# CW342_XADC.net
KiCad netlist of a schematic drawn in Altium Designer
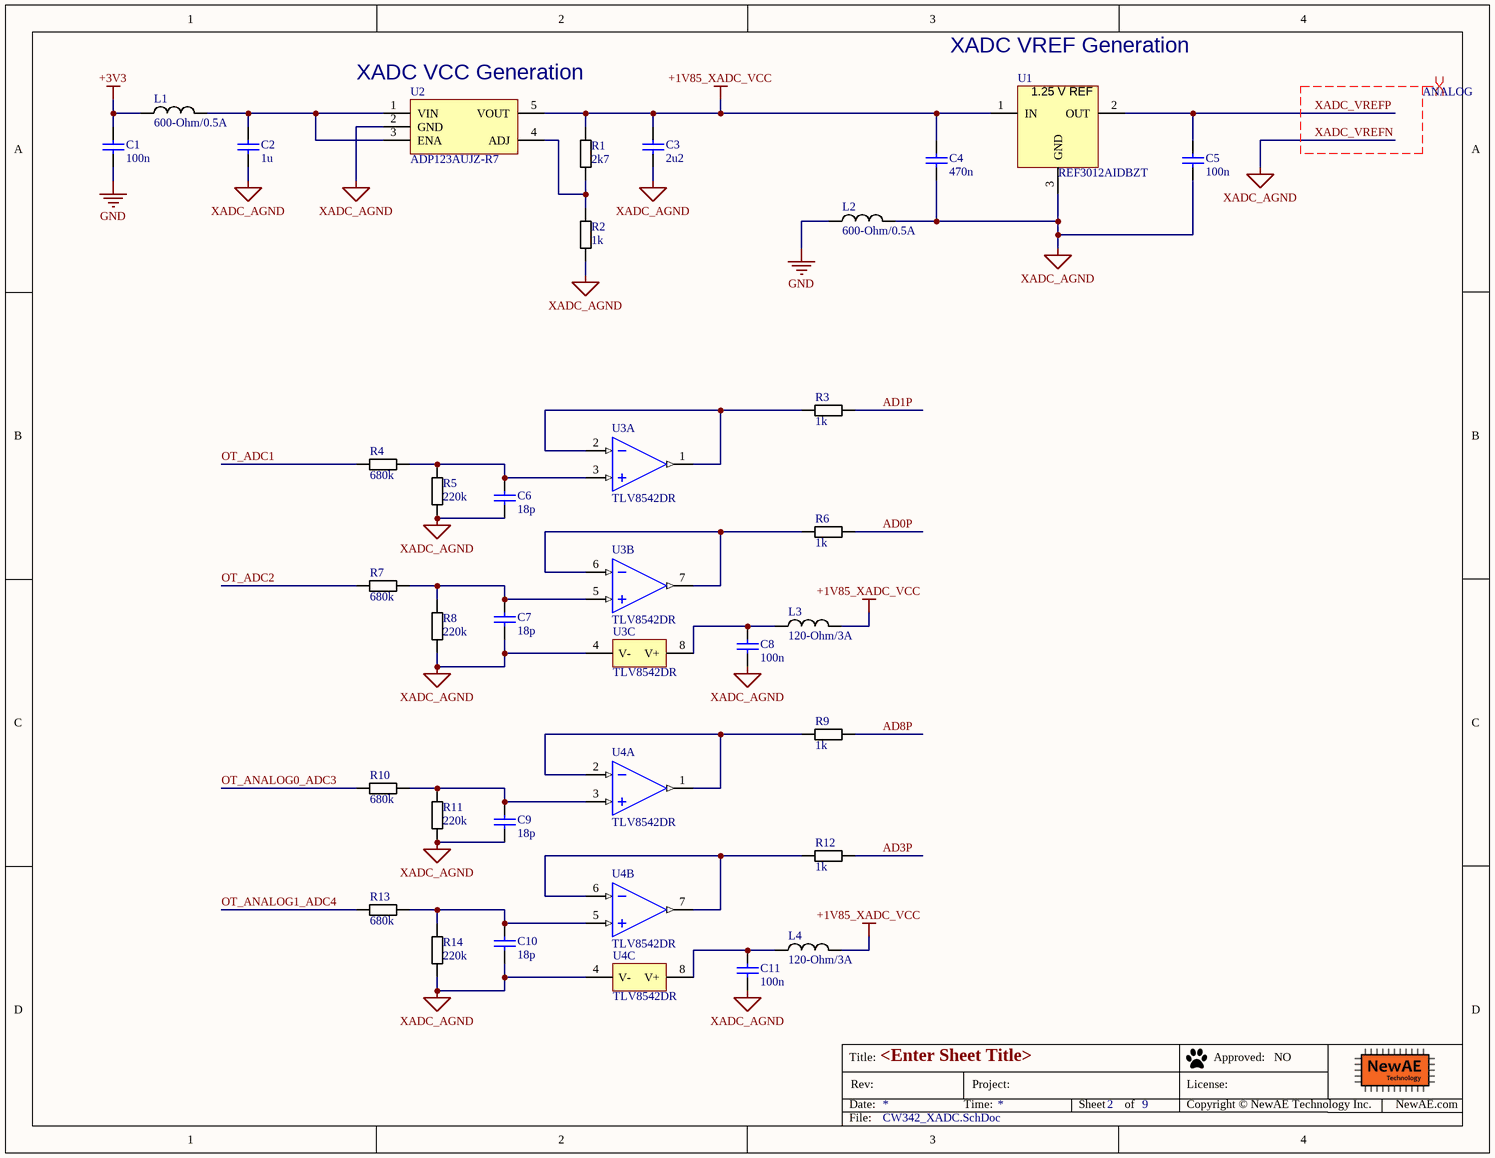
[diagram p0: CW342_XADC.SchDoc]

(export (version "E")
  (design (tool "Eeschema 10.0.6"))
  (components
    (comp (ref "C1")
      (value "100n")
      (footprint "CAPC0402_M")
      (description "100n, 0402")
      (fields (field (name "PART NUMBER") "CCHIP-100n-0402"))
      (libsource (lib "NewAE_AltiumLib") (part "CAP"))
    )
    (comp (ref "C2")
      (value "1u")
      (footprint "CAPC0603_M")
      (description "1u, 0603, 50V")
      (fields (field (name "PART NUMBER") "CCHIP-1u-0603"))
      (libsource (lib "NewAE_AltiumLib") (part "CAP"))
    )
    (comp (ref "C3")
      (value "2u2")
      (footprint "CAPC0603_M")
      (description "2u2, 0603")
      (fields (field (name "PART NUMBER") "CCHIP-2u2-0603-25V") (field (name "TOLERANCE") "±20%"))
      (libsource (lib "NewAE_AltiumLib") (part "CAP"))
    )
    (comp (ref "C4")
      (value "470n")
      (footprint "CAPC0603_M")
      (description "470n, 0603, 50V")
      (fields (field (name "PART NUMBER") "CCHIP-470n-0603-50V"))
      (libsource (lib "NewAE_AltiumLib") (part "CAP"))
    )
    (comp (ref "C5")
      (value "100n")
      (footprint "CAPC0402_M")
      (description "100n, 0402")
      (fields (field (name "PART NUMBER") "CCHIP-100n-0402"))
      (libsource (lib "NewAE_AltiumLib") (part "CAP"))
    )
    (comp (ref "C6")
      (value "18p")
      (footprint "CAPC0402_M")
      (description "18p, 0402")
      (fields (field (name "PART NUMBER") "CCHIP-18p-0402"))
      (libsource (lib "NewAE_AltiumLib") (part "CAP"))
    )
    (comp (ref "C7")
      (value "18p")
      (footprint "CAPC0402_M")
      (description "18p, 0402")
      (fields (field (name "PART NUMBER") "CCHIP-18p-0402"))
      (libsource (lib "NewAE_AltiumLib") (part "CAP"))
    )
    (comp (ref "C8")
      (value "100n")
      (footprint "CAPC0402_M")
      (description "100n, 0402")
      (fields (field (name "PART NUMBER") "CCHIP-100n-0402"))
      (libsource (lib "NewAE_AltiumLib") (part "CAP"))
    )
    (comp (ref "C9")
      (value "18p")
      (footprint "CAPC0402_M")
      (description "18p, 0402")
      (fields (field (name "PART NUMBER") "CCHIP-18p-0402"))
      (libsource (lib "NewAE_AltiumLib") (part "CAP"))
    )
    (comp (ref "C10")
      (value "18p")
      (footprint "CAPC0402_M")
      (description "18p, 0402")
      (fields (field (name "PART NUMBER") "CCHIP-18p-0402"))
      (libsource (lib "NewAE_AltiumLib") (part "CAP"))
    )
    (comp (ref "C11")
      (value "100n")
      (footprint "CAPC0402_M")
      (description "100n, 0402")
      (fields (field (name "PART NUMBER") "CCHIP-100n-0402"))
      (libsource (lib "NewAE_AltiumLib") (part "CAP"))
    )
    (comp (ref "L1")
      (value "600-Ohm/0.5A")
      (footprint "IND_0603")
      (description "600 Ohm @ 100 MHz, 0.5A rated FB")
      (fields (field (name "PART NUMBER") "FBCHIP-600R-0603"))
      (libsource (lib "NewAE_AltiumLib") (part "IND"))
    )
    (comp (ref "L2")
      (value "600-Ohm/0.5A")
      (footprint "IND_0603")
      (description "600 Ohm @ 100 MHz, 0.5A rated FB")
      (fields (field (name "PART NUMBER") "FBCHIP-600R-0603"))
      (libsource (lib "NewAE_AltiumLib") (part "IND"))
    )
    (comp (ref "L3")
      (value "120-Ohm/3A")
      (footprint "IND_0603")
      (description "120 Ohm @ 100 MHz, 3A rated FB")
      (fields (field (name "PART NUMBER") "FBCHIP-120R-0603"))
      (libsource (lib "NewAE_AltiumLib") (part "IND"))
    )
    (comp (ref "L4")
      (value "120-Ohm/3A")
      (footprint "IND_0603")
      (description "120 Ohm @ 100 MHz, 3A rated FB")
      (fields (field (name "PART NUMBER") "FBCHIP-120R-0603"))
      (libsource (lib "NewAE_AltiumLib") (part "IND"))
    )
    (comp (ref "R1")
      (value "2k7")
      (footprint "RESC1005X40N")
      (description "2k7 res, 0402, 1%, 1/16W")
      (fields (field (name "PART NUMBER") "RCHIP-2K7-0402") (field (name "TOLERANCE") "1%"))
      (libsource (lib "") (part "RES-EU_1"))
    )
    (comp (ref "R2")
      (value "1k")
      (footprint "RESC1005X40N")
      (description "1k res, 0402, 1%, 1/16W")
      (fields (field (name "PART NUMBER") "RCHIP-1K-0402") (field (name "TOLERANCE") "1%"))
      (libsource (lib "") (part "RES-EU_1"))
    )
    (comp (ref "R3")
      (value "1k")
      (footprint "RESC1005X40N")
      (description "1k res, 0402, 1%, 1/16W")
      (fields (field (name "PART NUMBER") "RCHIP-1K-0402") (field (name "TOLERANCE") "1%"))
      (libsource (lib "NewAE_AltiumLib") (part "RES-EU"))
    )
    (comp (ref "R4")
      (value "680k")
      (footprint "RESC1005X40N")
      (description "680k res, 0402, 1%, 1/16W")
      (fields (field (name "PART NUMBER") "RCHIP-680K-0402") (field (name "TOLERANCE") "1%"))
      (libsource (lib "NewAE_AltiumLib") (part "RES-EU"))
    )
    (comp (ref "R5")
      (value "220k")
      (footprint "RESC1005X40N")
      (description "220k res, 0402, 1%, 1/16W")
      (fields (field (name "PART NUMBER") "RCHIP-220K-0402") (field (name "TOLERANCE") "1%"))
      (libsource (lib "") (part "RES-EU_1"))
    )
    (comp (ref "R6")
      (value "1k")
      (footprint "RESC1005X40N")
      (description "1k res, 0402, 1%, 1/16W")
      (fields (field (name "PART NUMBER") "RCHIP-1K-0402") (field (name "TOLERANCE") "1%"))
      (libsource (lib "NewAE_AltiumLib") (part "RES-EU"))
    )
    (comp (ref "R7")
      (value "680k")
      (footprint "RESC1005X40N")
      (description "680k res, 0402, 1%, 1/16W")
      (fields (field (name "PART NUMBER") "RCHIP-680K-0402") (field (name "TOLERANCE") "1%"))
      (libsource (lib "NewAE_AltiumLib") (part "RES-EU"))
    )
    (comp (ref "R8")
      (value "220k")
      (footprint "RESC1005X40N")
      (description "220k res, 0402, 1%, 1/16W")
      (fields (field (name "PART NUMBER") "RCHIP-220K-0402") (field (name "TOLERANCE") "1%"))
      (libsource (lib "") (part "RES-EU_1"))
    )
    (comp (ref "R9")
      (value "1k")
      (footprint "RESC1005X40N")
      (description "1k res, 0402, 1%, 1/16W")
      (fields (field (name "PART NUMBER") "RCHIP-1K-0402") (field (name "TOLERANCE") "1%"))
      (libsource (lib "NewAE_AltiumLib") (part "RES-EU"))
    )
    (comp (ref "R10")
      (value "680k")
      (footprint "RESC1005X40N")
      (description "680k res, 0402, 1%, 1/16W")
      (fields (field (name "PART NUMBER") "RCHIP-680K-0402") (field (name "TOLERANCE") "1%"))
      (libsource (lib "NewAE_AltiumLib") (part "RES-EU"))
    )
    (comp (ref "R11")
      (value "220k")
      (footprint "RESC1005X40N")
      (description "220k res, 0402, 1%, 1/16W")
      (fields (field (name "PART NUMBER") "RCHIP-220K-0402") (field (name "TOLERANCE") "1%"))
      (libsource (lib "") (part "RES-EU_1"))
    )
    (comp (ref "R12")
      (value "1k")
      (footprint "RESC1005X40N")
      (description "1k res, 0402, 1%, 1/16W")
      (fields (field (name "PART NUMBER") "RCHIP-1K-0402") (field (name "TOLERANCE") "1%"))
      (libsource (lib "NewAE_AltiumLib") (part "RES-EU"))
    )
    (comp (ref "R13")
      (value "680k")
      (footprint "RESC1005X40N")
      (description "680k res, 0402, 1%, 1/16W")
      (fields (field (name "PART NUMBER") "RCHIP-680K-0402") (field (name "TOLERANCE") "1%"))
      (libsource (lib "NewAE_AltiumLib") (part "RES-EU"))
    )
    (comp (ref "R14")
      (value "220k")
      (footprint "RESC1005X40N")
      (description "220k res, 0402, 1%, 1/16W")
      (fields (field (name "PART NUMBER") "RCHIP-220K-0402") (field (name "TOLERANCE") "1%"))
      (libsource (lib "") (part "RES-EU_1"))
    )
    (comp (ref "U1")
      (value "REF3012AIDBZT")
      (footprint "SOT95P237X112-3N")
      (description "IC VREF SERIES 0.2% SOT23-3")
      (fields (field (name "MANUFACTURER PART NUMBER") "REF3012AIDBZT"))
      (libsource (lib "NewAE_AltiumLib") (part "REF3012AIDBZT"))
    )
    (comp (ref "U2")
      (value "Linear Voltage Regulator IC  1 Output  300mA TSOT-5")
      (footprint "SOT23-5P95_285X145L45X40")
      (description "IC REG LIN POS ADJ 300MA TSOT5")
      (fields
        (field (name "MANUFACTURER PART NUMBER") "ADP123AUJZ-R7")
        (field (name "PART NUMBER") "ADP123AUJZ-R7")
      )
      (libsource (lib "NewAE_AltiumLib") (part "ADP123AUJZ-R7"))
    )
    (comp (ref "U3")
      (value "TLV8542DR")
      (footprint "SOIC127P600X175-8N")
      (description "IC OPAMP GP 700KHZ 8SOIC")
      (fields (field (name "PART NUMBER") "LM2904_SOIC8"))
      (libsource (lib "NewAE_AltiumLib") (part "LM2904"))
    )
    (comp (ref "U4")
      (value "TLV8542DR")
      (footprint "SOIC127P600X175-8N")
      (description "IC OP-AMP GP")
      (fields (field (name "PART NUMBER") "LM2904_SOIC8"))
      (libsource (lib "NewAE_AltiumLib") (part "LM2904"))
    )
  )
  (nets
    (net (code "1") (name "+1V85_XADC_VCC") (class "Default")
      (node (ref "C3") (pin "1") (pinfunction "1_1") (pintype "passive"))
      (node (ref "C4") (pin "1") (pinfunction "1_1") (pintype "passive"))
      (node (ref "L3") (pin "2") (pinfunction "2_2") (pintype "passive"))
      (node (ref "L4") (pin "2") (pinfunction "2_2") (pintype "passive"))
      (node (ref "R1") (pin "1") (pinfunction "1_1") (pintype "passive"))
      (node (ref "U1") (pin "1") (pinfunction "IN_1") (pintype "passive"))
      (node (ref "U2") (pin "5") (pinfunction "VOUT_5") (pintype "passive"))
    )
    (net (code "2") (name "+3V3") (class "Default")
      (node (ref "C1") (pin "1") (pinfunction "1_1") (pintype "passive"))
      (node (ref "L1") (pin "1") (pinfunction "1_1") (pintype "passive"))
    )
    (net (code "3") (name "/AD0P") (class "Default")
      (node (ref "R6") (pin "2") (pinfunction "2_2") (pintype "passive"))
    )
    (net (code "4") (name "/AD1P") (class "Default")
      (node (ref "R3") (pin "2") (pinfunction "2_2") (pintype "passive"))
    )
    (net (code "5") (name "/AD3P") (class "Default")
      (node (ref "R12") (pin "2") (pinfunction "2_2") (pintype "passive"))
    )
    (net (code "6") (name "/AD8P") (class "Default")
      (node (ref "R9") (pin "2") (pinfunction "2_2") (pintype "passive"))
    )
    (net (code "7") (name "/OT_ADC1") (class "Default")
      (node (ref "R4") (pin "1") (pinfunction "1_1") (pintype "passive"))
    )
    (net (code "8") (name "/OT_ADC2") (class "Default")
      (node (ref "R7") (pin "1") (pinfunction "1_1") (pintype "passive"))
    )
    (net (code "9") (name "/OT_ANALOG0_ADC3") (class "Default")
      (node (ref "R10") (pin "1") (pinfunction "1_1") (pintype "passive"))
    )
    (net (code "10") (name "/OT_ANALOG1_ADC4") (class "Default")
      (node (ref "R13") (pin "1") (pinfunction "1_1") (pintype "passive"))
    )
    (net (code "11") (name "/XADC_VREFP") (class "Default")
      (node (ref "C5") (pin "1") (pinfunction "1_1") (pintype "passive"))
      (node (ref "U1") (pin "2") (pinfunction "OUT_2") (pintype "passive"))
    )
    (net (code "12") (name "GND") (class "Default")
      (node (ref "C1") (pin "2") (pinfunction "2_2") (pintype "passive"))
      (node (ref "L2") (pin "1") (pinfunction "1_1") (pintype "passive"))
    )
    (net (code "13") (name "Net-(U2-ADJ)") (class "Default")
      (node (ref "R1") (pin "2") (pinfunction "2_2") (pintype "passive"))
      (node (ref "R2") (pin "1") (pinfunction "1_1") (pintype "passive"))
      (node (ref "U2") (pin "4") (pinfunction "ADJ_4") (pintype "passive"))
    )
    (net (code "14") (name "Net-(U2-ENA)") (class "Default")
      (node (ref "C2") (pin "1") (pinfunction "1_1") (pintype "passive"))
      (node (ref "L1") (pin "2") (pinfunction "2_2") (pintype "passive"))
      (node (ref "U2") (pin "1") (pinfunction "VIN_1") (pintype "passive"))
      (node (ref "U2") (pin "3") (pinfunction "ENA_3") (pintype "passive"))
    )
    (net (code "15") (name "Net-(U3A-1_IN+)") (class "Default")
      (node (ref "C6") (pin "1") (pinfunction "1_1") (pintype "passive"))
      (node (ref "R4") (pin "2") (pinfunction "2_2") (pintype "passive"))
      (node (ref "R5") (pin "1") (pinfunction "1_1") (pintype "passive"))
      (node (ref "U3") (pin "3") (pinfunction "1_IN+_3") (pintype "input"))
    )
    (net (code "16") (name "Net-(U3A-1_IN-)") (class "Default")
      (node (ref "R3") (pin "1") (pinfunction "1_1") (pintype "passive"))
      (node (ref "U3") (pin "1") (pinfunction "1_Out_1") (pintype "output"))
      (node (ref "U3") (pin "2") (pinfunction "1_IN-_2") (pintype "input"))
    )
    (net (code "17") (name "Net-(U3B-2_IN+)") (class "Default")
      (node (ref "C7") (pin "1") (pinfunction "1_1") (pintype "passive"))
      (node (ref "R7") (pin "2") (pinfunction "2_2") (pintype "passive"))
      (node (ref "R8") (pin "1") (pinfunction "1_1") (pintype "passive"))
      (node (ref "U3") (pin "5") (pinfunction "2_IN+_5") (pintype "input"))
    )
    (net (code "18") (name "Net-(U3B-2_IN-)") (class "Default")
      (node (ref "R6") (pin "1") (pinfunction "1_1") (pintype "passive"))
      (node (ref "U3") (pin "6") (pinfunction "2_IN-_6") (pintype "input"))
      (node (ref "U3") (pin "7") (pinfunction "2_Out_7") (pintype "output"))
    )
    (net (code "19") (name "Net-(U3C-V+)") (class "Default")
      (node (ref "C8") (pin "1") (pinfunction "1_1") (pintype "passive"))
      (node (ref "L3") (pin "1") (pinfunction "1_1") (pintype "passive"))
      (node (ref "U3") (pin "8") (pinfunction "V+_8") (pintype "passive"))
    )
    (net (code "20") (name "Net-(U4A-1_IN+)") (class "Default")
      (node (ref "C9") (pin "1") (pinfunction "1_1") (pintype "passive"))
      (node (ref "R10") (pin "2") (pinfunction "2_2") (pintype "passive"))
      (node (ref "R11") (pin "1") (pinfunction "1_1") (pintype "passive"))
      (node (ref "U4") (pin "3") (pinfunction "1_IN+_3") (pintype "input"))
    )
    (net (code "21") (name "Net-(U4A-1_IN-)") (class "Default")
      (node (ref "R9") (pin "1") (pinfunction "1_1") (pintype "passive"))
      (node (ref "U4") (pin "1") (pinfunction "1_Out_1") (pintype "output"))
      (node (ref "U4") (pin "2") (pinfunction "1_IN-_2") (pintype "input"))
    )
    (net (code "22") (name "Net-(U4B-2_IN+)") (class "Default")
      (node (ref "C10") (pin "1") (pinfunction "1_1") (pintype "passive"))
      (node (ref "R13") (pin "2") (pinfunction "2_2") (pintype "passive"))
      (node (ref "R14") (pin "1") (pinfunction "1_1") (pintype "passive"))
      (node (ref "U4") (pin "5") (pinfunction "2_IN+_5") (pintype "input"))
    )
    (net (code "23") (name "Net-(U4B-2_IN-)") (class "Default")
      (node (ref "R12") (pin "1") (pinfunction "1_1") (pintype "passive"))
      (node (ref "U4") (pin "6") (pinfunction "2_IN-_6") (pintype "input"))
      (node (ref "U4") (pin "7") (pinfunction "2_Out_7") (pintype "output"))
    )
    (net (code "24") (name "Net-(U4C-V+)") (class "Default")
      (node (ref "C11") (pin "1") (pinfunction "1_1") (pintype "passive"))
      (node (ref "L4") (pin "1") (pinfunction "1_1") (pintype "passive"))
      (node (ref "U4") (pin "8") (pinfunction "V+_8") (pintype "passive"))
    )
    (net (code "25") (name "XADC_AGND") (class "Default")
      (node (ref "C10") (pin "2") (pinfunction "2_2") (pintype "passive"))
      (node (ref "C11") (pin "2") (pinfunction "2_2") (pintype "passive"))
      (node (ref "C2") (pin "2") (pinfunction "2_2") (pintype "passive"))
      (node (ref "C3") (pin "2") (pinfunction "2_2") (pintype "passive"))
      (node (ref "C4") (pin "2") (pinfunction "2_2") (pintype "passive"))
      (node (ref "C5") (pin "2") (pinfunction "2_2") (pintype "passive"))
      (node (ref "C6") (pin "2") (pinfunction "2_2") (pintype "passive"))
      (node (ref "C7") (pin "2") (pinfunction "2_2") (pintype "passive"))
      (node (ref "C8") (pin "2") (pinfunction "2_2") (pintype "passive"))
      (node (ref "C9") (pin "2") (pinfunction "2_2") (pintype "passive"))
      (node (ref "L2") (pin "2") (pinfunction "2_2") (pintype "passive"))
      (node (ref "R11") (pin "2") (pinfunction "2_2") (pintype "passive"))
      (node (ref "R14") (pin "2") (pinfunction "2_2") (pintype "passive"))
      (node (ref "R2") (pin "2") (pinfunction "2_2") (pintype "passive"))
      (node (ref "R5") (pin "2") (pinfunction "2_2") (pintype "passive"))
      (node (ref "R8") (pin "2") (pinfunction "2_2") (pintype "passive"))
      (node (ref "U1") (pin "3") (pinfunction "GND_3") (pintype "passive"))
      (node (ref "U2") (pin "2") (pinfunction "GND_2") (pintype "passive"))
      (node (ref "U3") (pin "4") (pinfunction "V-_4") (pintype "power_in"))
      (node (ref "U4") (pin "4") (pinfunction "V-_4") (pintype "power_in"))
    )
  )
)
